# 9_TEMP.net
KiCad netlist of a schematic drawn in Altium Designer
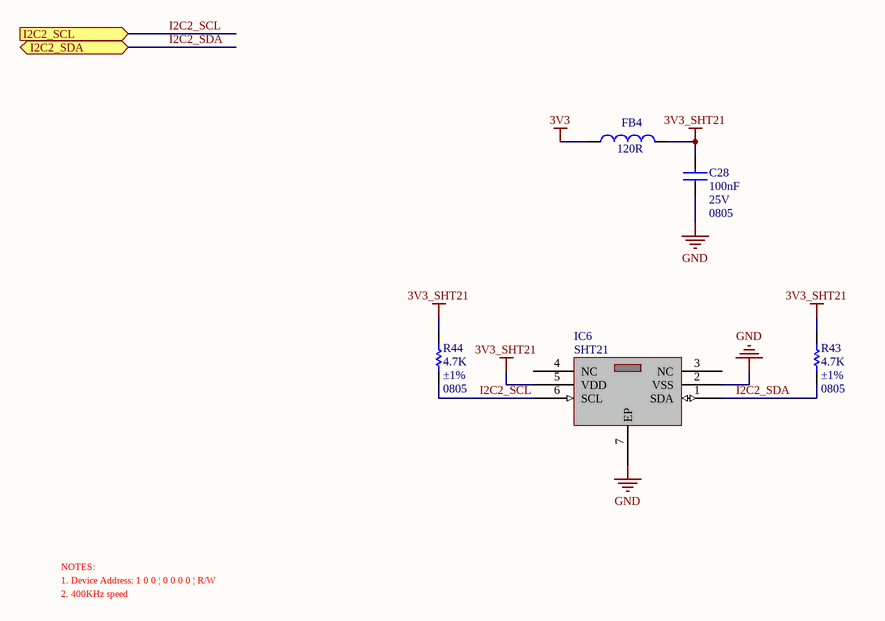
[diagram p0: 9.TEMP.SchDoc]

(export (version "E")
  (design (tool "Eeschema 10.0.6"))
  (components
    (comp (ref "C28")
      (value "CAP_NP")
      (footprint "CAPC2012X100N_EIA0805")
      (description "CAP CER 0.1UF 25V X7R 0805")
      (fields
        (field (name "PART NUMBER") "SCAP00300093")
        (field (name "CAPACITANCE") "100nF")
        (field (name "TOLERANCE") "±10%")
        (field (name "VOLTAGE - RATED") "25V")
        (field (name "PACKAGE / CASE") "0805")
      )
      (libsource (lib "ComponentDatabase") (part "CAP_NP"))
    )
    (comp (ref "FB4")
      (value "BEAD")
      (footprint "FILC2012X100N_EIA0805")
      (description "FERRITE CHIP POWER 120 OHM SMD")
      (fields
        (field (name "PART NUMBER") "SFIL00005")
        (field (name "IMPEDANCE") "120R")
        (field (name "MANUFACTURER") "Laird-Signal Integrity Products")
      )
      (libsource (lib "ComponentDatabase") (part "BEAD"))
    )
    (comp (ref "IC6")
      (value "SHT21")
      (footprint "SHT21")
      (description "HUMIDITY AND TEMPERATURE SENSOR")
      (fields
        (field (name "PART NUMBER") "SSEN00014")
        (field (name "VOLTAGE") "2.1 V ~ 3.6 V")
        (field (name "MANUFACTURER PART NUMBER") "SHT21")
      )
      (libsource (lib "ComponentDatabase") (part "SHT21"))
    )
    (comp (ref "R43")
      (value "RES")
      (footprint "RESC2013X65N_EIA0805")
      (description "RES SMD 4.7K OHM 1% 1/8W 0805")
      (fields
        (field (name "PART NUMBER") "SRES03010090")
        (field (name "RESISTANCE (OHM)") "4.7K")
        (field (name "TOLERANCE") "±1%")
        (field (name "PACKAGE / CASE") "0805")
        (field (name "MANUFACTURER") "Yageo")
      )
      (libsource (lib "ComponentDatabase") (part "RES"))
    )
    (comp (ref "R44")
      (value "RES")
      (footprint "RESC2013X65N_EIA0805")
      (description "RES SMD 4.7K OHM 1% 1/8W 0805")
      (fields
        (field (name "PART NUMBER") "SRES03010090")
        (field (name "RESISTANCE (OHM)") "4.7K")
        (field (name "TOLERANCE") "±1%")
        (field (name "PACKAGE / CASE") "0805")
        (field (name "MANUFACTURER") "Yageo")
      )
      (libsource (lib "ComponentDatabase") (part "RES"))
    )
  )
  (nets
    (net (code "1") (name "/I2C2_SCL") (class "Default")
      (node (ref "IC6") (pin "6") (pinfunction "SCL_6") (pintype "input"))
      (node (ref "R44") (pin "1") (pinfunction "1_1") (pintype "passive"))
    )
    (net (code "2") (name "/I2C2_SDA") (class "Default")
      (node (ref "IC6") (pin "1") (pinfunction "SDA_1") (pintype "bidirectional"))
      (node (ref "R43") (pin "1") (pinfunction "1_1") (pintype "passive"))
    )
    (net (code "3") (name "3V3") (class "Default")
      (node (ref "FB4") (pin "1") (pinfunction "1_1") (pintype "passive"))
    )
    (net (code "4") (name "3V3_SHT21") (class "Default")
      (node (ref "C28") (pin "2") (pinfunction "2_2") (pintype "passive"))
      (node (ref "FB4") (pin "2") (pinfunction "2_2") (pintype "passive"))
      (node (ref "IC6") (pin "5") (pinfunction "VDD_5") (pintype "power_in"))
      (node (ref "R43") (pin "2") (pinfunction "2_2") (pintype "passive"))
      (node (ref "R44") (pin "2") (pinfunction "2_2") (pintype "passive"))
    )
    (net (code "5") (name "GND") (class "Default")
      (node (ref "C28") (pin "1") (pinfunction "1_1") (pintype "passive"))
      (node (ref "IC6") (pin "2") (pinfunction "VSS_2") (pintype "power_in"))
      (node (ref "IC6") (pin "7") (pinfunction "EP_7") (pintype "passive"))
    )
    (net (code "6") (name "unconnected-(IC6-NC-Pad3)") (class "Default")
      (node (ref "IC6") (pin "3") (pinfunction "NC_3") (pintype "passive"))
    )
    (net (code "7") (name "unconnected-(IC6-NC-Pad4)") (class "Default")
      (node (ref "IC6") (pin "4") (pinfunction "NC_4") (pintype "passive"))
    )
  )
)
